# untitled.net
KiCad netlist of a schematic drawn in EAGLE
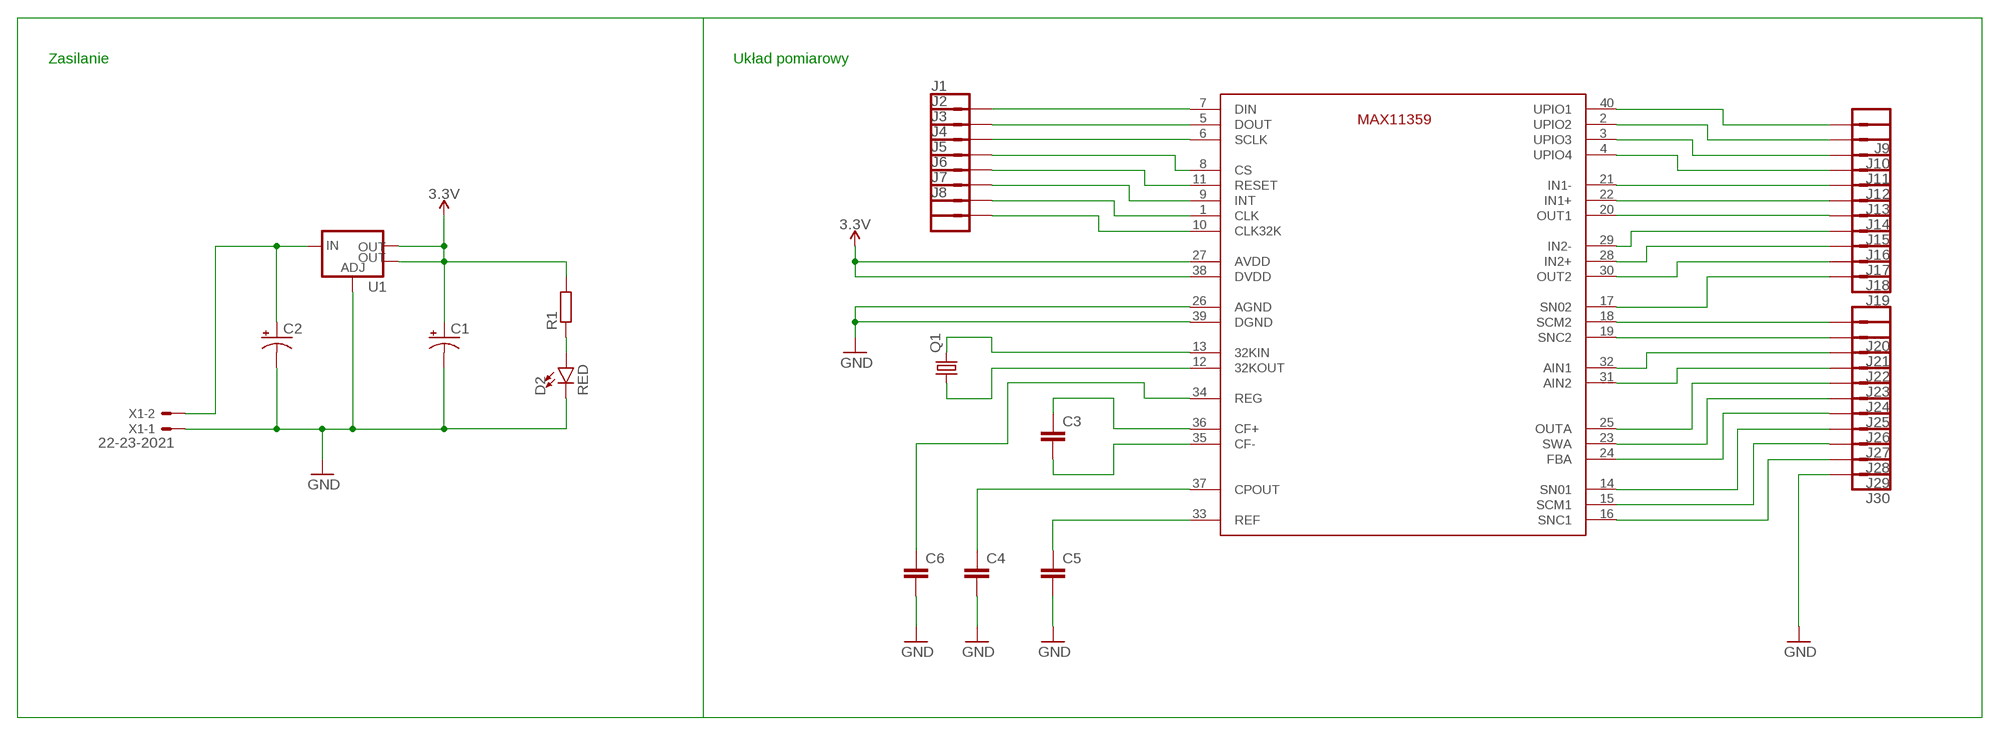
[diagram p0: schematic, sheet 1]

(export (version "E")
  (design (tool "Eeschema 10.0.6"))
  (components
    (comp (ref "C1")
      (value "CPOL-US140CLH-1010")
      (footprint "eagle-import:140CLH-1010")
      (libsource (lib "eagle-import") (part "CPOL-US140CLH-1010"))
    )
    (comp (ref "C2")
      (value "CPOL-US140CLH-1010")
      (footprint "eagle-import:140CLH-1010")
      (libsource (lib "eagle-import") (part "CPOL-US140CLH-1010"))
    )
    (comp (ref "C3")
      (value "C-EUC0805")
      (footprint "eagle-import:C0805")
      (libsource (lib "eagle-import") (part "C-EUC0805"))
    )
    (comp (ref "C4")
      (value "C-EUC0805")
      (footprint "eagle-import:C0805")
      (libsource (lib "eagle-import") (part "C-EUC0805"))
    )
    (comp (ref "C5")
      (value "C-EUC0805")
      (footprint "eagle-import:C0805")
      (libsource (lib "eagle-import") (part "C-EUC0805"))
    )
    (comp (ref "C6")
      (value "C-EUC0805")
      (footprint "eagle-import:C0805")
      (libsource (lib "eagle-import") (part "C-EUC0805"))
    )
    (comp (ref "D2")
      (value "RED")
      (footprint "eagle-import:LED-1206")
      (libsource (lib "eagle-import") (part "LED-RED1206"))
    )
    (comp (ref "J1")
      (value "CONN_01")
      (footprint "eagle-import:1X01")
      (libsource (lib "eagle-import") (part "CONN_01"))
    )
    (comp (ref "J2")
      (value "CONN_01")
      (footprint "eagle-import:1X01")
      (libsource (lib "eagle-import") (part "CONN_01"))
    )
    (comp (ref "J3")
      (value "CONN_01")
      (footprint "eagle-import:1X01")
      (libsource (lib "eagle-import") (part "CONN_01"))
    )
    (comp (ref "J4")
      (value "CONN_01")
      (footprint "eagle-import:1X01")
      (libsource (lib "eagle-import") (part "CONN_01"))
    )
    (comp (ref "J5")
      (value "CONN_01")
      (footprint "eagle-import:1X01")
      (libsource (lib "eagle-import") (part "CONN_01"))
    )
    (comp (ref "J6")
      (value "CONN_01")
      (footprint "eagle-import:1X01")
      (libsource (lib "eagle-import") (part "CONN_01"))
    )
    (comp (ref "J7")
      (value "CONN_01")
      (footprint "eagle-import:1X01")
      (libsource (lib "eagle-import") (part "CONN_01"))
    )
    (comp (ref "J8")
      (value "CONN_01")
      (footprint "eagle-import:1X01")
      (libsource (lib "eagle-import") (part "CONN_01"))
    )
    (comp (ref "J9")
      (value "CONN_01")
      (footprint "eagle-import:1X01")
      (libsource (lib "eagle-import") (part "CONN_01"))
    )
    (comp (ref "J10")
      (value "CONN_01")
      (footprint "eagle-import:1X01")
      (libsource (lib "eagle-import") (part "CONN_01"))
    )
    (comp (ref "J11")
      (value "CONN_01")
      (footprint "eagle-import:1X01")
      (libsource (lib "eagle-import") (part "CONN_01"))
    )
    (comp (ref "J12")
      (value "CONN_01")
      (footprint "eagle-import:1X01")
      (libsource (lib "eagle-import") (part "CONN_01"))
    )
    (comp (ref "J13")
      (value "CONN_01")
      (footprint "eagle-import:1X01")
      (libsource (lib "eagle-import") (part "CONN_01"))
    )
    (comp (ref "J14")
      (value "CONN_01")
      (footprint "eagle-import:1X01")
      (libsource (lib "eagle-import") (part "CONN_01"))
    )
    (comp (ref "J15")
      (value "CONN_01")
      (footprint "eagle-import:1X01")
      (libsource (lib "eagle-import") (part "CONN_01"))
    )
    (comp (ref "J16")
      (value "CONN_01")
      (footprint "eagle-import:1X01")
      (libsource (lib "eagle-import") (part "CONN_01"))
    )
    (comp (ref "J17")
      (value "CONN_01")
      (footprint "eagle-import:1X01")
      (libsource (lib "eagle-import") (part "CONN_01"))
    )
    (comp (ref "J18")
      (value "CONN_01")
      (footprint "eagle-import:1X01")
      (libsource (lib "eagle-import") (part "CONN_01"))
    )
    (comp (ref "J19")
      (value "CONN_01")
      (footprint "eagle-import:1X01")
      (libsource (lib "eagle-import") (part "CONN_01"))
    )
    (comp (ref "J20")
      (value "CONN_01")
      (footprint "eagle-import:1X01")
      (libsource (lib "eagle-import") (part "CONN_01"))
    )
    (comp (ref "J21")
      (value "CONN_01")
      (footprint "eagle-import:1X01")
      (libsource (lib "eagle-import") (part "CONN_01"))
    )
    (comp (ref "J22")
      (value "CONN_01")
      (footprint "eagle-import:1X01")
      (libsource (lib "eagle-import") (part "CONN_01"))
    )
    (comp (ref "J23")
      (value "CONN_01")
      (footprint "eagle-import:1X01")
      (libsource (lib "eagle-import") (part "CONN_01"))
    )
    (comp (ref "J24")
      (value "CONN_01")
      (footprint "eagle-import:1X01")
      (libsource (lib "eagle-import") (part "CONN_01"))
    )
    (comp (ref "J25")
      (value "CONN_01")
      (footprint "eagle-import:1X01")
      (libsource (lib "eagle-import") (part "CONN_01"))
    )
    (comp (ref "J26")
      (value "CONN_01")
      (footprint "eagle-import:1X01")
      (libsource (lib "eagle-import") (part "CONN_01"))
    )
    (comp (ref "J27")
      (value "CONN_01")
      (footprint "eagle-import:1X01")
      (libsource (lib "eagle-import") (part "CONN_01"))
    )
    (comp (ref "J28")
      (value "CONN_01")
      (footprint "eagle-import:1X01")
      (libsource (lib "eagle-import") (part "CONN_01"))
    )
    (comp (ref "J29")
      (value "CONN_01")
      (footprint "eagle-import:1X01")
      (libsource (lib "eagle-import") (part "CONN_01"))
    )
    (comp (ref "J30")
      (value "CONN_01")
      (footprint "eagle-import:1X01")
      (libsource (lib "eagle-import") (part "CONN_01"))
    )
    (comp (ref "Q1")
      (value "CRYSTALHC49UP")
      (footprint "eagle-import:HC49UP")
      (libsource (lib "eagle-import") (part "CRYSTALHC49UP"))
    )
    (comp (ref "R1")
      (value "R-EU_M0805")
      (footprint "eagle-import:M0805")
      (libsource (lib "eagle-import") (part "R-EU_M0805"))
    )
    (comp (ref "U$1")
      (value "MAX11359A")
      (footprint "eagle-import:TQFN")
      (libsource (lib "eagle-import") (part "MAX11359A"))
    )
    (comp (ref "U1")
      (value "V_REG_LM1117SOT223")
      (footprint "eagle-import:SOT223")
      (libsource (lib "eagle-import") (part "V_REG_LM1117SOT223"))
    )
    (comp (ref "X1")
      (value "22-23-2021")
      (footprint "eagle-import:22-23-2021")
      (fields (field (name "MF") "MOLEX"))
      (libsource (lib "eagle-import") (part "22-23-2021"))
    )
  )
  (nets
    (net (code "1") (name "3.3V") (class "Default")
      (node (ref "C1") (pin "+") (pinfunction "+_+") (pintype "passive"))
      (node (ref "R1") (pin "2") (pinfunction "2_2") (pintype "passive"))
      (node (ref "U$1") (pin "27") (pinfunction "AVDD_27") (pintype "bidirectional"))
      (node (ref "U$1") (pin "38") (pinfunction "DVDD_38") (pintype "bidirectional"))
      (node (ref "U1") (pin "2") (pinfunction "OUT_2") (pintype "output"))
      (node (ref "U1") (pin "4") (pinfunction "OUT_4") (pintype "output"))
    )
    (net (code "2") (name "GND") (class "Default")
      (node (ref "C1") (pin "-") (pinfunction "-_-") (pintype "passive"))
      (node (ref "C2") (pin "-") (pinfunction "-_-") (pintype "passive"))
      (node (ref "C4") (pin "2") (pinfunction "2_2") (pintype "passive"))
      (node (ref "C5") (pin "2") (pinfunction "2_2") (pintype "passive"))
      (node (ref "C6") (pin "2") (pinfunction "2_2") (pintype "passive"))
      (node (ref "D2") (pin "C") (pinfunction "C_C") (pintype "passive"))
      (node (ref "J30") (pin "1") (pinfunction "1_1") (pintype "passive"))
      (node (ref "U$1") (pin "26") (pinfunction "AGND_26") (pintype "bidirectional"))
      (node (ref "U$1") (pin "39") (pinfunction "DGND_39") (pintype "bidirectional"))
      (node (ref "U1") (pin "1") (pinfunction "ADJ_1") (pintype "input"))
      (node (ref "X1") (pin "1") (pinfunction "S_1") (pintype "passive"))
    )
    (net (code "3") (name "Net-(D2-PadA)") (class "Default")
      (node (ref "D2") (pin "A") (pinfunction "A_A") (pintype "passive"))
      (node (ref "R1") (pin "1") (pinfunction "1_1") (pintype "passive"))
    )
    (net (code "4") (name "Net-(U$1-32KIN)") (class "Default")
      (node (ref "Q1") (pin "2") (pinfunction "2_2") (pintype "passive"))
      (node (ref "U$1") (pin "13") (pinfunction "32KIN_13") (pintype "bidirectional"))
    )
    (net (code "5") (name "Net-(U$1-32KOUT)") (class "Default")
      (node (ref "Q1") (pin "1") (pinfunction "1_1") (pintype "passive"))
      (node (ref "U$1") (pin "12") (pinfunction "32KOUT_12") (pintype "bidirectional"))
    )
    (net (code "6") (name "Net-(U$1-AIN1)") (class "Default")
      (node (ref "J22") (pin "1") (pinfunction "1_1") (pintype "passive"))
      (node (ref "U$1") (pin "32") (pinfunction "AIN1_32") (pintype "bidirectional"))
    )
    (net (code "7") (name "Net-(U$1-AIN2)") (class "Default")
      (node (ref "J23") (pin "1") (pinfunction "1_1") (pintype "passive"))
      (node (ref "U$1") (pin "31") (pinfunction "AIN2_31") (pintype "bidirectional"))
    )
    (net (code "8") (name "Net-(U$1-CF+)") (class "Default")
      (node (ref "C3") (pin "1") (pinfunction "1_1") (pintype "passive"))
      (node (ref "U$1") (pin "36") (pinfunction "CF+_36") (pintype "bidirectional"))
    )
    (net (code "9") (name "Net-(U$1-CF-)") (class "Default")
      (node (ref "C3") (pin "2") (pinfunction "2_2") (pintype "passive"))
      (node (ref "U$1") (pin "35") (pinfunction "CF-_35") (pintype "bidirectional"))
    )
    (net (code "10") (name "Net-(U$1-CLK)") (class "Default")
      (node (ref "J7") (pin "1") (pinfunction "1_1") (pintype "passive"))
      (node (ref "U$1") (pin "1") (pinfunction "CLK_1") (pintype "bidirectional"))
    )
    (net (code "11") (name "Net-(U$1-CLK32K)") (class "Default")
      (node (ref "J8") (pin "1") (pinfunction "1_1") (pintype "passive"))
      (node (ref "U$1") (pin "10") (pinfunction "CLK32K_10") (pintype "bidirectional"))
    )
    (net (code "12") (name "Net-(U$1-CPOUT)") (class "Default")
      (node (ref "C4") (pin "1") (pinfunction "1_1") (pintype "passive"))
      (node (ref "U$1") (pin "37") (pinfunction "CPOUT_37") (pintype "bidirectional"))
    )
    (net (code "13") (name "Net-(U$1-CS)") (class "Default")
      (node (ref "J4") (pin "1") (pinfunction "1_1") (pintype "passive"))
      (node (ref "U$1") (pin "8") (pinfunction "CS_8") (pintype "bidirectional"))
    )
    (net (code "14") (name "Net-(U$1-DIN)") (class "Default")
      (node (ref "J1") (pin "1") (pinfunction "1_1") (pintype "passive"))
      (node (ref "U$1") (pin "7") (pinfunction "DIN_7") (pintype "bidirectional"))
    )
    (net (code "15") (name "Net-(U$1-DOUT)") (class "Default")
      (node (ref "J2") (pin "1") (pinfunction "1_1") (pintype "passive"))
      (node (ref "U$1") (pin "5") (pinfunction "DOUT_5") (pintype "bidirectional"))
    )
    (net (code "16") (name "Net-(U$1-FBA)") (class "Default")
      (node (ref "J26") (pin "1") (pinfunction "1_1") (pintype "passive"))
      (node (ref "U$1") (pin "24") (pinfunction "FBA_24") (pintype "bidirectional"))
    )
    (net (code "17") (name "Net-(U$1-IN1+)") (class "Default")
      (node (ref "J14") (pin "1") (pinfunction "1_1") (pintype "passive"))
      (node (ref "U$1") (pin "22") (pinfunction "IN1+_22") (pintype "bidirectional"))
    )
    (net (code "18") (name "Net-(U$1-IN1-)") (class "Default")
      (node (ref "J13") (pin "1") (pinfunction "1_1") (pintype "passive"))
      (node (ref "U$1") (pin "21") (pinfunction "IN1-_21") (pintype "bidirectional"))
    )
    (net (code "19") (name "Net-(U$1-IN2+)") (class "Default")
      (node (ref "J17") (pin "1") (pinfunction "1_1") (pintype "passive"))
      (node (ref "U$1") (pin "28") (pinfunction "IN2+_28") (pintype "bidirectional"))
    )
    (net (code "20") (name "Net-(U$1-IN2-)") (class "Default")
      (node (ref "J16") (pin "1") (pinfunction "1_1") (pintype "passive"))
      (node (ref "U$1") (pin "29") (pinfunction "IN2-_29") (pintype "bidirectional"))
    )
    (net (code "21") (name "Net-(U$1-INT)") (class "Default")
      (node (ref "J6") (pin "1") (pinfunction "1_1") (pintype "passive"))
      (node (ref "U$1") (pin "9") (pinfunction "INT_9") (pintype "bidirectional"))
    )
    (net (code "22") (name "Net-(U$1-OUT1)") (class "Default")
      (node (ref "J15") (pin "1") (pinfunction "1_1") (pintype "passive"))
      (node (ref "U$1") (pin "20") (pinfunction "OUT1_20") (pintype "bidirectional"))
    )
    (net (code "23") (name "Net-(U$1-OUT2)") (class "Default")
      (node (ref "J18") (pin "1") (pinfunction "1_1") (pintype "passive"))
      (node (ref "U$1") (pin "30") (pinfunction "OUT2_30") (pintype "bidirectional"))
    )
    (net (code "24") (name "Net-(U$1-OUTA)") (class "Default")
      (node (ref "J24") (pin "1") (pinfunction "1_1") (pintype "passive"))
      (node (ref "U$1") (pin "25") (pinfunction "OUTA_25") (pintype "bidirectional"))
    )
    (net (code "25") (name "Net-(U$1-REF)") (class "Default")
      (node (ref "C5") (pin "1") (pinfunction "1_1") (pintype "passive"))
      (node (ref "U$1") (pin "33") (pinfunction "REF_33") (pintype "bidirectional"))
    )
    (net (code "26") (name "Net-(U$1-REG)") (class "Default")
      (node (ref "C6") (pin "1") (pinfunction "1_1") (pintype "passive"))
      (node (ref "U$1") (pin "34") (pinfunction "REG_34") (pintype "bidirectional"))
    )
    (net (code "27") (name "Net-(U$1-RESET)") (class "Default")
      (node (ref "J5") (pin "1") (pinfunction "1_1") (pintype "passive"))
      (node (ref "U$1") (pin "11") (pinfunction "RESET_11") (pintype "bidirectional"))
    )
    (net (code "28") (name "Net-(U$1-SCLK)") (class "Default")
      (node (ref "J3") (pin "1") (pinfunction "1_1") (pintype "passive"))
      (node (ref "U$1") (pin "6") (pinfunction "SCLK_6") (pintype "bidirectional"))
    )
    (net (code "29") (name "Net-(U$1-SCM1)") (class "Default")
      (node (ref "J28") (pin "1") (pinfunction "1_1") (pintype "passive"))
      (node (ref "U$1") (pin "15") (pinfunction "SCM1_15") (pintype "bidirectional"))
    )
    (net (code "30") (name "Net-(U$1-SCM2)") (class "Default")
      (node (ref "J20") (pin "1") (pinfunction "1_1") (pintype "passive"))
      (node (ref "U$1") (pin "18") (pinfunction "SCM2_18") (pintype "bidirectional"))
    )
    (net (code "31") (name "Net-(U$1-SN01)") (class "Default")
      (node (ref "J27") (pin "1") (pinfunction "1_1") (pintype "passive"))
      (node (ref "U$1") (pin "14") (pinfunction "SN01_14") (pintype "bidirectional"))
    )
    (net (code "32") (name "Net-(U$1-SN02)") (class "Default")
      (node (ref "J19") (pin "1") (pinfunction "1_1") (pintype "passive"))
      (node (ref "U$1") (pin "17") (pinfunction "SN02_17") (pintype "bidirectional"))
    )
    (net (code "33") (name "Net-(U$1-SNC1)") (class "Default")
      (node (ref "J29") (pin "1") (pinfunction "1_1") (pintype "passive"))
      (node (ref "U$1") (pin "16") (pinfunction "SNC1_16") (pintype "bidirectional"))
    )
    (net (code "34") (name "Net-(U$1-SNC2)") (class "Default")
      (node (ref "J21") (pin "1") (pinfunction "1_1") (pintype "passive"))
      (node (ref "U$1") (pin "19") (pinfunction "SNC2_19") (pintype "bidirectional"))
    )
    (net (code "35") (name "Net-(U$1-SWA)") (class "Default")
      (node (ref "J25") (pin "1") (pinfunction "1_1") (pintype "passive"))
      (node (ref "U$1") (pin "23") (pinfunction "SWA_23") (pintype "bidirectional"))
    )
    (net (code "36") (name "Net-(U$1-UPIO1)") (class "Default")
      (node (ref "J9") (pin "1") (pinfunction "1_1") (pintype "passive"))
      (node (ref "U$1") (pin "40") (pinfunction "UPIO1_40") (pintype "bidirectional"))
    )
    (net (code "37") (name "Net-(U$1-UPIO2)") (class "Default")
      (node (ref "J10") (pin "1") (pinfunction "1_1") (pintype "passive"))
      (node (ref "U$1") (pin "2") (pinfunction "UPIO2_2") (pintype "bidirectional"))
    )
    (net (code "38") (name "Net-(U$1-UPIO3)") (class "Default")
      (node (ref "J11") (pin "1") (pinfunction "1_1") (pintype "passive"))
      (node (ref "U$1") (pin "3") (pinfunction "UPIO3_3") (pintype "bidirectional"))
    )
    (net (code "39") (name "Net-(U$1-UPIO4)") (class "Default")
      (node (ref "J12") (pin "1") (pinfunction "1_1") (pintype "passive"))
      (node (ref "U$1") (pin "4") (pinfunction "UPIO4_4") (pintype "bidirectional"))
    )
    (net (code "40") (name "Net-(U1-IN)") (class "Default")
      (node (ref "C2") (pin "+") (pinfunction "+_+") (pintype "passive"))
      (node (ref "U1") (pin "3") (pinfunction "IN_3") (pintype "input"))
      (node (ref "X1") (pin "2") (pinfunction "S_2") (pintype "passive"))
    )
  )
)
